# S7CAS-PLEIADES-CARTE-MERE_Pxx_POWER_FPGA.net
KiCad netlist of a schematic drawn in Altium Designer
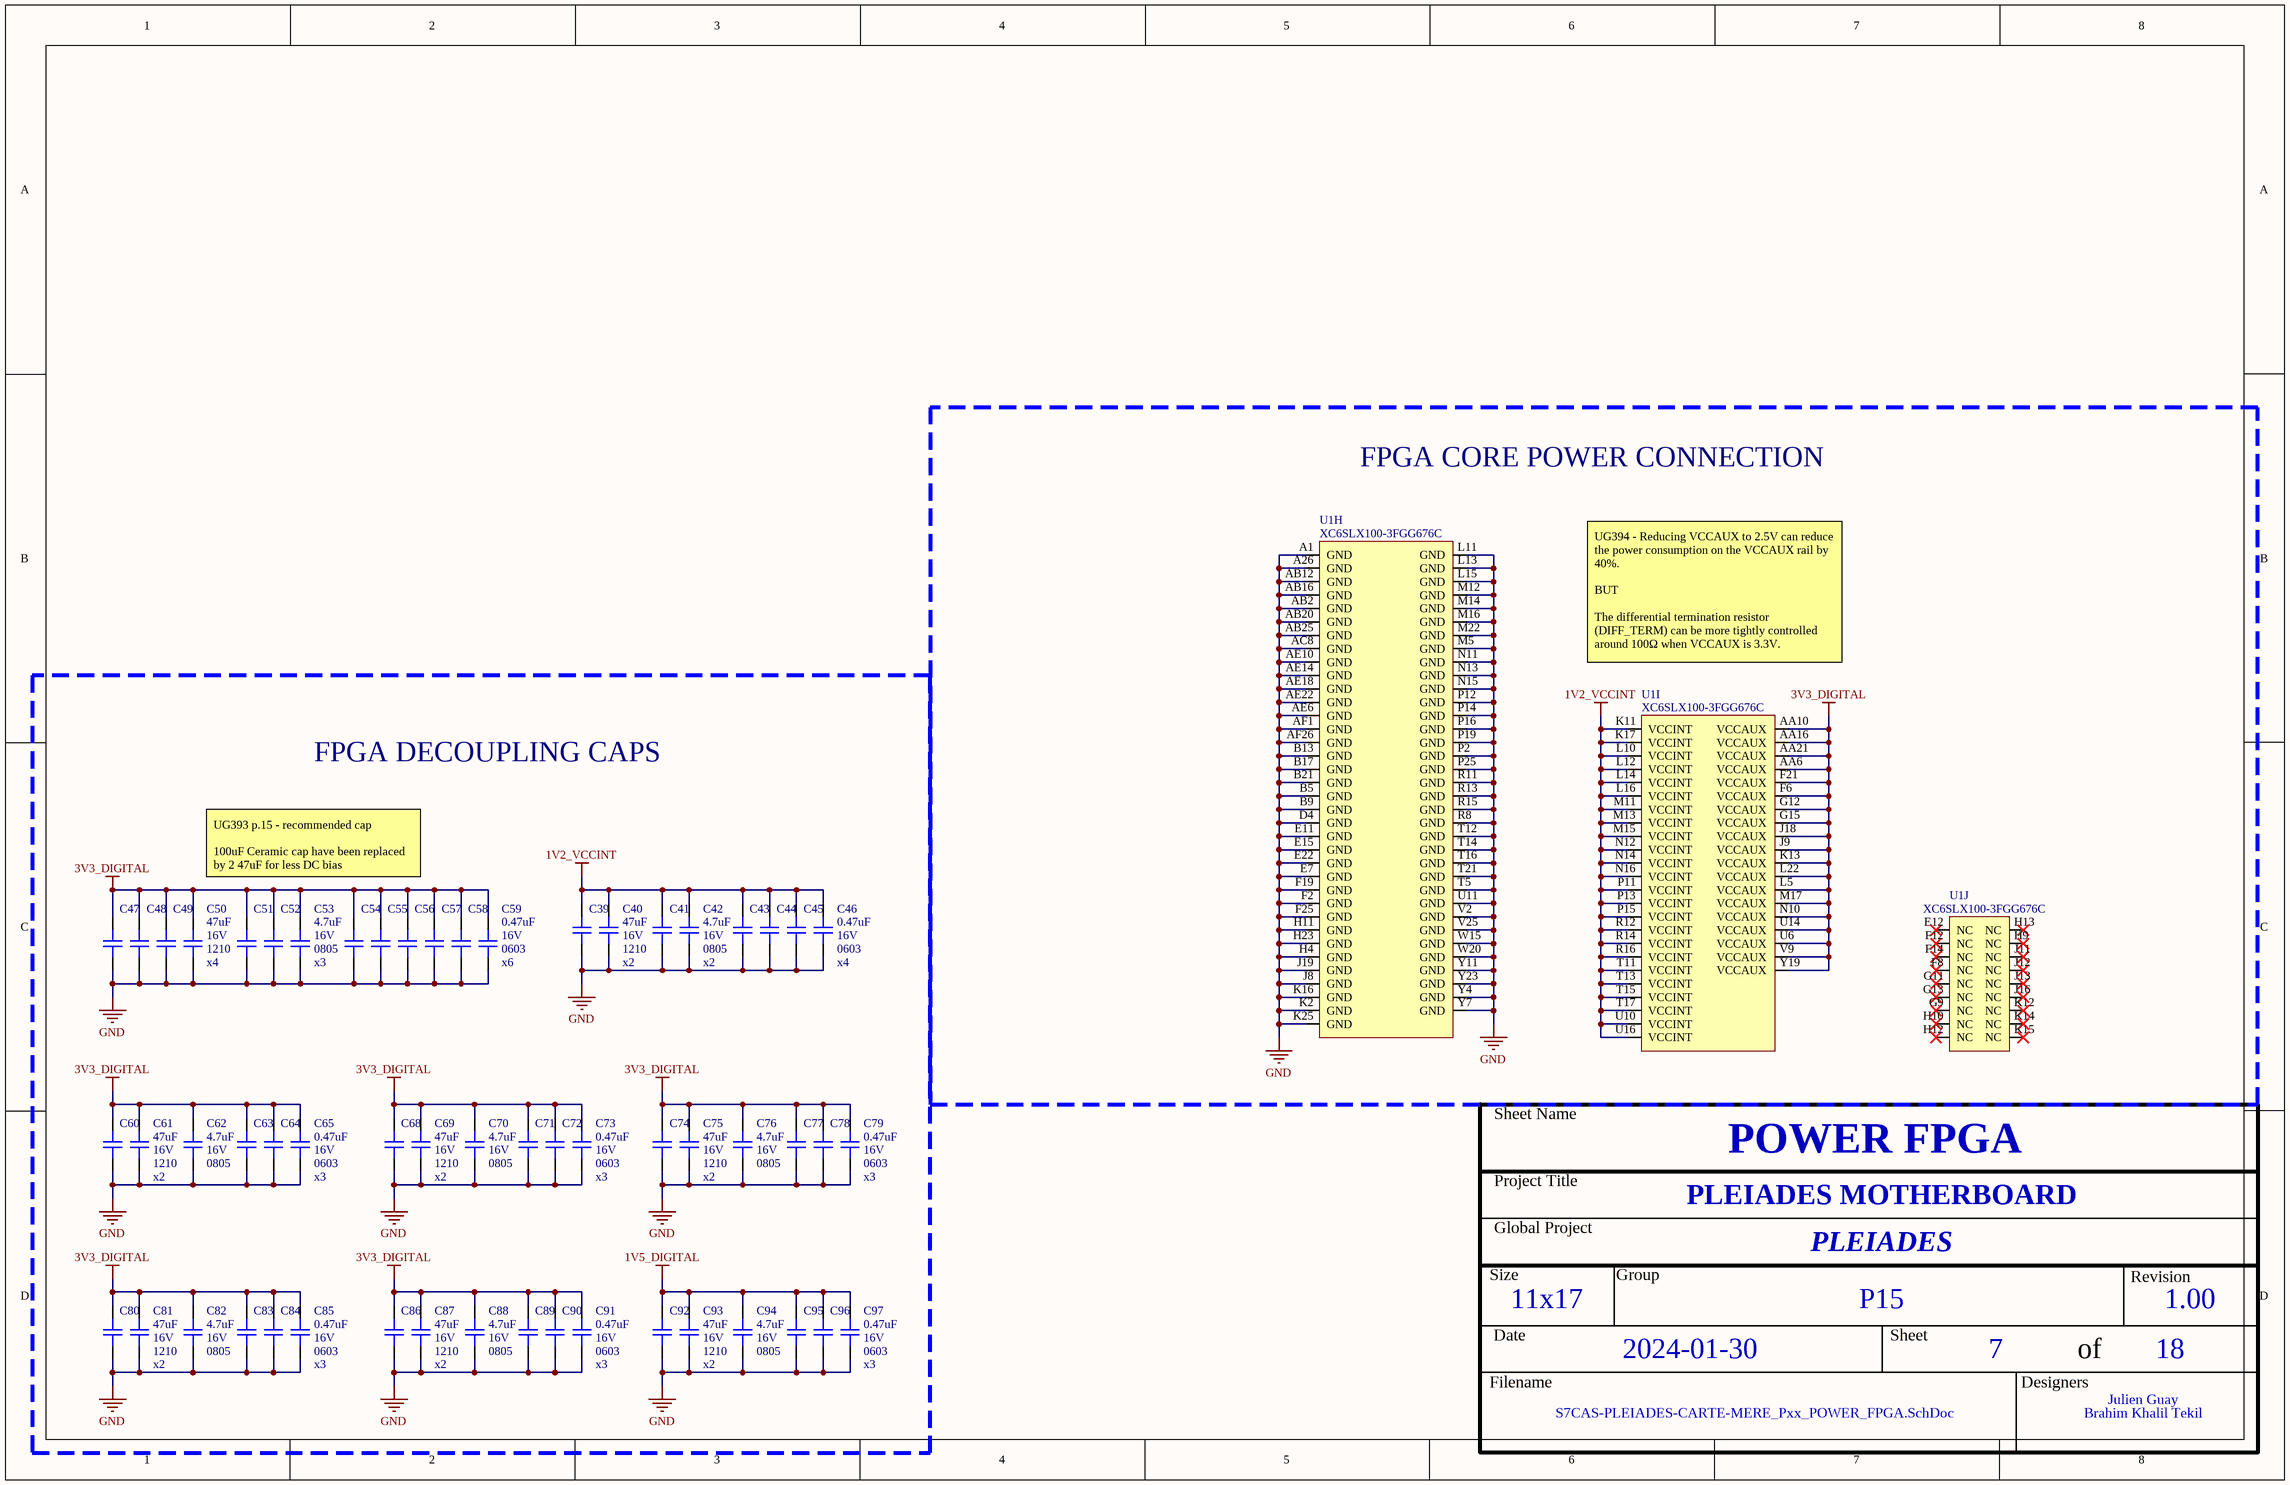
[diagram p0: S7CAS-PLEIADES-CARTE-MERE_Pxx_POWER_FPGA.SchDoc]

(export (version "E")
  (design (tool "Eeschema 10.0.6"))
  (components
    (comp (ref "C39")
      (value "CAP - 1210")
      (footprint "CAP_1210")
      (fields (field (name "VOLTAGE") "16V") (field (name "CREATEDBY") "Jonathan Bouchard"))
      (libsource (lib "S7CAS_LIB2023") (part "CAP - 1210"))
    )
    (comp (ref "C40")
      (value "47uF")
      (footprint "CAP_1210")
      (description "CAP - 1210")
      (fields
        (field (name "VOLTAGE") "16V")
        (field (name "PACKAGE") "1210")
        (field (name "CREATEDBY") "Jonathan Bouchard")
      )
      (libsource (lib "S7CAS_LIB2023") (part "CAP - 1210"))
    )
    (comp (ref "C41")
      (value "CAP - 0805")
      (footprint "CAP_0805")
      (fields (field (name "VOLTAGE") "16V") (field (name "CREATEDBY") "Jonathan Bouchard"))
      (libsource (lib "S7CAS_LIB2023") (part "CAP - 0805"))
    )
    (comp (ref "C42")
      (value "4.7uF")
      (footprint "CAP_0805")
      (description "CAP - 0805")
      (fields
        (field (name "VOLTAGE") "16V")
        (field (name "PACKAGE") "0805")
        (field (name "CREATEDBY") "Jonathan Bouchard")
      )
      (libsource (lib "S7CAS_LIB2023") (part "CAP - 0805"))
    )
    (comp (ref "C43")
      (value "CAP - 0603")
      (footprint "CAP_0603")
      (fields (field (name "VOLTAGE") "16V") (field (name "CREATEDBY") "Jonathan Bouchard"))
      (libsource (lib "S7CAS_LIB2023") (part "CAP - 0603"))
    )
    (comp (ref "C44")
      (value "CAP - 0603")
      (footprint "CAP_0603")
      (fields (field (name "VOLTAGE") "16V") (field (name "CREATEDBY") "Jonathan Bouchard"))
      (libsource (lib "S7CAS_LIB2023") (part "CAP - 0603"))
    )
    (comp (ref "C45")
      (value "CAP - 0603")
      (footprint "CAP_0603")
      (fields (field (name "VOLTAGE") "16V") (field (name "CREATEDBY") "Jonathan Bouchard"))
      (libsource (lib "S7CAS_LIB2023") (part "CAP - 0603"))
    )
    (comp (ref "C46")
      (value "0.47uF")
      (footprint "CAP_0603")
      (description "CAP - 0603")
      (fields
        (field (name "VOLTAGE") "16V")
        (field (name "PACKAGE") "0603")
        (field (name "CREATEDBY") "Jonathan Bouchard")
      )
      (libsource (lib "S7CAS_LIB2023") (part "CAP - 0603"))
    )
    (comp (ref "C47")
      (value "CAP - 1210")
      (footprint "CAP_1210")
      (fields (field (name "VOLTAGE") "16V") (field (name "CREATEDBY") "Jonathan Bouchard"))
      (libsource (lib "S7CAS_LIB2023") (part "CAP - 1210"))
    )
    (comp (ref "C48")
      (value "CAP - 1210")
      (footprint "CAP_1210")
      (fields (field (name "VOLTAGE") "16V") (field (name "CREATEDBY") "Jonathan Bouchard"))
      (libsource (lib "S7CAS_LIB2023") (part "CAP - 1210"))
    )
    (comp (ref "C49")
      (value "CAP - 1210")
      (footprint "CAP_1210")
      (fields (field (name "VOLTAGE") "16V") (field (name "CREATEDBY") "Jonathan Bouchard"))
      (libsource (lib "S7CAS_LIB2023") (part "CAP - 1210"))
    )
    (comp (ref "C50")
      (value "47uF")
      (footprint "CAP_1210")
      (description "CAP - 1210")
      (fields
        (field (name "VOLTAGE") "16V")
        (field (name "PACKAGE") "1210")
        (field (name "CREATEDBY") "Jonathan Bouchard")
      )
      (libsource (lib "S7CAS_LIB2023") (part "CAP - 1210"))
    )
    (comp (ref "C51")
      (value "CAP - 0805")
      (footprint "CAP_0805")
      (fields (field (name "VOLTAGE") "16V") (field (name "CREATEDBY") "Jonathan Bouchard"))
      (libsource (lib "S7CAS_LIB2023") (part "CAP - 0805"))
    )
    (comp (ref "C52")
      (value "CAP - 0805")
      (footprint "CAP_0805")
      (fields (field (name "VOLTAGE") "16V") (field (name "CREATEDBY") "Jonathan Bouchard"))
      (libsource (lib "S7CAS_LIB2023") (part "CAP - 0805"))
    )
    (comp (ref "C53")
      (value "4.7uF")
      (footprint "CAP_0805")
      (description "CAP - 0805")
      (fields
        (field (name "VOLTAGE") "16V")
        (field (name "PACKAGE") "0805")
        (field (name "CREATEDBY") "Jonathan Bouchard")
      )
      (libsource (lib "S7CAS_LIB2023") (part "CAP - 0805"))
    )
    (comp (ref "C54")
      (value "CAP - 0603")
      (footprint "CAP_0603")
      (fields (field (name "VOLTAGE") "16V") (field (name "CREATEDBY") "Jonathan Bouchard"))
      (libsource (lib "S7CAS_LIB2023") (part "CAP - 0603"))
    )
    (comp (ref "C55")
      (value "CAP - 0603")
      (footprint "CAP_0603")
      (fields (field (name "VOLTAGE") "16V") (field (name "CREATEDBY") "Jonathan Bouchard"))
      (libsource (lib "S7CAS_LIB2023") (part "CAP - 0603"))
    )
    (comp (ref "C56")
      (value "CAP - 0603")
      (footprint "CAP_0603")
      (fields (field (name "VOLTAGE") "16V") (field (name "CREATEDBY") "Jonathan Bouchard"))
      (libsource (lib "S7CAS_LIB2023") (part "CAP - 0603"))
    )
    (comp (ref "C57")
      (value "CAP - 0603")
      (footprint "CAP_0603")
      (fields (field (name "VOLTAGE") "16V") (field (name "CREATEDBY") "Jonathan Bouchard"))
      (libsource (lib "S7CAS_LIB2023") (part "CAP - 0603"))
    )
    (comp (ref "C58")
      (value "CAP - 0603")
      (footprint "CAP_0603")
      (fields (field (name "VOLTAGE") "16V") (field (name "CREATEDBY") "Jonathan Bouchard"))
      (libsource (lib "S7CAS_LIB2023") (part "CAP - 0603"))
    )
    (comp (ref "C59")
      (value "0.47uF")
      (footprint "CAP_0603")
      (description "CAP - 0603")
      (fields
        (field (name "VOLTAGE") "16V")
        (field (name "PACKAGE") "0603")
        (field (name "CREATEDBY") "Jonathan Bouchard")
      )
      (libsource (lib "S7CAS_LIB2023") (part "CAP - 0603"))
    )
    (comp (ref "C60")
      (value "CAP - 1210")
      (footprint "CAP_1210")
      (fields (field (name "VOLTAGE") "16V") (field (name "CREATEDBY") "Jonathan Bouchard"))
      (libsource (lib "S7CAS_LIB2023") (part "CAP - 1210"))
    )
    (comp (ref "C61")
      (value "47uF")
      (footprint "CAP_1210")
      (description "CAP - 1210")
      (fields
        (field (name "VOLTAGE") "16V")
        (field (name "PACKAGE") "1210")
        (field (name "CREATEDBY") "Jonathan Bouchard")
      )
      (libsource (lib "S7CAS_LIB2023") (part "CAP - 1210"))
    )
    (comp (ref "C62")
      (value "4.7uF")
      (footprint "CAP_0805")
      (description "CAP - 0805")
      (fields
        (field (name "VOLTAGE") "16V")
        (field (name "PACKAGE") "0805")
        (field (name "CREATEDBY") "Jonathan Bouchard")
      )
      (libsource (lib "S7CAS_LIB2023") (part "CAP - 0805"))
    )
    (comp (ref "C63")
      (value "CAP - 0603")
      (footprint "CAP_0603")
      (fields (field (name "VOLTAGE") "16V") (field (name "CREATEDBY") "Jonathan Bouchard"))
      (libsource (lib "S7CAS_LIB2023") (part "CAP - 0603"))
    )
    (comp (ref "C64")
      (value "CAP - 0603")
      (footprint "CAP_0603")
      (fields (field (name "VOLTAGE") "16V") (field (name "CREATEDBY") "Jonathan Bouchard"))
      (libsource (lib "S7CAS_LIB2023") (part "CAP - 0603"))
    )
    (comp (ref "C65")
      (value "0.47uF")
      (footprint "CAP_0603")
      (description "CAP - 0603")
      (fields
        (field (name "VOLTAGE") "16V")
        (field (name "PACKAGE") "0603")
        (field (name "CREATEDBY") "Jonathan Bouchard")
      )
      (libsource (lib "S7CAS_LIB2023") (part "CAP - 0603"))
    )
    (comp (ref "C68")
      (value "CAP - 1210")
      (footprint "CAP_1210")
      (fields (field (name "VOLTAGE") "16V") (field (name "CREATEDBY") "Jonathan Bouchard"))
      (libsource (lib "S7CAS_LIB2023") (part "CAP - 1210"))
    )
    (comp (ref "C69")
      (value "47uF")
      (footprint "CAP_1210")
      (description "CAP - 1210")
      (fields
        (field (name "VOLTAGE") "16V")
        (field (name "PACKAGE") "1210")
        (field (name "CREATEDBY") "Jonathan Bouchard")
      )
      (libsource (lib "S7CAS_LIB2023") (part "CAP - 1210"))
    )
    (comp (ref "C70")
      (value "4.7uF")
      (footprint "CAP_0805")
      (description "CAP - 0805")
      (fields
        (field (name "VOLTAGE") "16V")
        (field (name "PACKAGE") "0805")
        (field (name "CREATEDBY") "Jonathan Bouchard")
      )
      (libsource (lib "S7CAS_LIB2023") (part "CAP - 0805"))
    )
    (comp (ref "C71")
      (value "CAP - 0603")
      (footprint "CAP_0603")
      (fields (field (name "VOLTAGE") "16V") (field (name "CREATEDBY") "Jonathan Bouchard"))
      (libsource (lib "S7CAS_LIB2023") (part "CAP - 0603"))
    )
    (comp (ref "C72")
      (value "CAP - 0603")
      (footprint "CAP_0603")
      (fields (field (name "VOLTAGE") "16V") (field (name "CREATEDBY") "Jonathan Bouchard"))
      (libsource (lib "S7CAS_LIB2023") (part "CAP - 0603"))
    )
    (comp (ref "C73")
      (value "0.47uF")
      (footprint "CAP_0603")
      (description "CAP - 0603")
      (fields
        (field (name "VOLTAGE") "16V")
        (field (name "PACKAGE") "0603")
        (field (name "CREATEDBY") "Jonathan Bouchard")
      )
      (libsource (lib "S7CAS_LIB2023") (part "CAP - 0603"))
    )
    (comp (ref "C74")
      (value "CAP - 1210")
      (footprint "CAP_1210")
      (fields (field (name "VOLTAGE") "16V") (field (name "CREATEDBY") "Jonathan Bouchard"))
      (libsource (lib "S7CAS_LIB2023") (part "CAP - 1210"))
    )
    (comp (ref "C75")
      (value "47uF")
      (footprint "CAP_1210")
      (description "CAP - 1210")
      (fields
        (field (name "VOLTAGE") "16V")
        (field (name "PACKAGE") "1210")
        (field (name "CREATEDBY") "Jonathan Bouchard")
      )
      (libsource (lib "S7CAS_LIB2023") (part "CAP - 1210"))
    )
    (comp (ref "C76")
      (value "4.7uF")
      (footprint "CAP_0805")
      (description "CAP - 0805")
      (fields
        (field (name "VOLTAGE") "16V")
        (field (name "PACKAGE") "0805")
        (field (name "CREATEDBY") "Jonathan Bouchard")
      )
      (libsource (lib "S7CAS_LIB2023") (part "CAP - 0805"))
    )
    (comp (ref "C77")
      (value "CAP - 0603")
      (footprint "CAP_0603")
      (fields (field (name "VOLTAGE") "16V") (field (name "CREATEDBY") "Jonathan Bouchard"))
      (libsource (lib "S7CAS_LIB2023") (part "CAP - 0603"))
    )
    (comp (ref "C78")
      (value "CAP - 0603")
      (footprint "CAP_0603")
      (fields (field (name "VOLTAGE") "16V") (field (name "CREATEDBY") "Jonathan Bouchard"))
      (libsource (lib "S7CAS_LIB2023") (part "CAP - 0603"))
    )
    (comp (ref "C79")
      (value "0.47uF")
      (footprint "CAP_0603")
      (description "CAP - 0603")
      (fields
        (field (name "VOLTAGE") "16V")
        (field (name "PACKAGE") "0603")
        (field (name "CREATEDBY") "Jonathan Bouchard")
      )
      (libsource (lib "S7CAS_LIB2023") (part "CAP - 0603"))
    )
    (comp (ref "C80")
      (value "CAP - 1210")
      (footprint "CAP_1210")
      (fields (field (name "VOLTAGE") "16V") (field (name "CREATEDBY") "Jonathan Bouchard"))
      (libsource (lib "S7CAS_LIB2023") (part "CAP - 1210"))
    )
    (comp (ref "C81")
      (value "47uF")
      (footprint "CAP_1210")
      (description "CAP - 1210")
      (fields
        (field (name "VOLTAGE") "16V")
        (field (name "PACKAGE") "1210")
        (field (name "CREATEDBY") "Jonathan Bouchard")
      )
      (libsource (lib "S7CAS_LIB2023") (part "CAP - 1210"))
    )
    (comp (ref "C82")
      (value "4.7uF")
      (footprint "CAP_0805")
      (description "CAP - 0805")
      (fields
        (field (name "VOLTAGE") "16V")
        (field (name "PACKAGE") "0805")
        (field (name "CREATEDBY") "Jonathan Bouchard")
      )
      (libsource (lib "S7CAS_LIB2023") (part "CAP - 0805"))
    )
    (comp (ref "C83")
      (value "CAP - 0603")
      (footprint "CAP_0603")
      (fields (field (name "VOLTAGE") "16V") (field (name "CREATEDBY") "Jonathan Bouchard"))
      (libsource (lib "S7CAS_LIB2023") (part "CAP - 0603"))
    )
    (comp (ref "C84")
      (value "CAP - 0603")
      (footprint "CAP_0603")
      (fields (field (name "VOLTAGE") "16V") (field (name "CREATEDBY") "Jonathan Bouchard"))
      (libsource (lib "S7CAS_LIB2023") (part "CAP - 0603"))
    )
    (comp (ref "C85")
      (value "0.47uF")
      (footprint "CAP_0603")
      (description "CAP - 0603")
      (fields
        (field (name "VOLTAGE") "16V")
        (field (name "PACKAGE") "0603")
        (field (name "CREATEDBY") "Jonathan Bouchard")
      )
      (libsource (lib "S7CAS_LIB2023") (part "CAP - 0603"))
    )
    (comp (ref "C86")
      (value "CAP - 1210")
      (footprint "CAP_1210")
      (fields (field (name "VOLTAGE") "16V") (field (name "CREATEDBY") "Jonathan Bouchard"))
      (libsource (lib "S7CAS_LIB2023") (part "CAP - 1210"))
    )
    (comp (ref "C87")
      (value "47uF")
      (footprint "CAP_1210")
      (description "CAP - 1210")
      (fields
        (field (name "VOLTAGE") "16V")
        (field (name "PACKAGE") "1210")
        (field (name "CREATEDBY") "Jonathan Bouchard")
      )
      (libsource (lib "S7CAS_LIB2023") (part "CAP - 1210"))
    )
    (comp (ref "C88")
      (value "4.7uF")
      (footprint "CAP_0805")
      (description "CAP - 0805")
      (fields
        (field (name "VOLTAGE") "16V")
        (field (name "PACKAGE") "0805")
        (field (name "CREATEDBY") "Jonathan Bouchard")
      )
      (libsource (lib "S7CAS_LIB2023") (part "CAP - 0805"))
    )
    (comp (ref "C89")
      (value "CAP - 0603")
      (footprint "CAP_0603")
      (fields (field (name "VOLTAGE") "16V") (field (name "CREATEDBY") "Jonathan Bouchard"))
      (libsource (lib "S7CAS_LIB2023") (part "CAP - 0603"))
    )
    (comp (ref "C90")
      (value "CAP - 0603")
      (footprint "CAP_0603")
      (fields (field (name "VOLTAGE") "16V") (field (name "CREATEDBY") "Jonathan Bouchard"))
      (libsource (lib "S7CAS_LIB2023") (part "CAP - 0603"))
    )
    (comp (ref "C91")
      (value "0.47uF")
      (footprint "CAP_0603")
      (description "CAP - 0603")
      (fields
        (field (name "VOLTAGE") "16V")
        (field (name "PACKAGE") "0603")
        (field (name "CREATEDBY") "Jonathan Bouchard")
      )
      (libsource (lib "S7CAS_LIB2023") (part "CAP - 0603"))
    )
    (comp (ref "C92")
      (value "CAP - 1210")
      (footprint "CAP_1210")
      (fields (field (name "VOLTAGE") "16V") (field (name "CREATEDBY") "Jonathan Bouchard"))
      (libsource (lib "S7CAS_LIB2023") (part "CAP - 1210"))
    )
    (comp (ref "C93")
      (value "47uF")
      (footprint "CAP_1210")
      (description "CAP - 1210")
      (fields
        (field (name "VOLTAGE") "16V")
        (field (name "PACKAGE") "1210")
        (field (name "CREATEDBY") "Jonathan Bouchard")
      )
      (libsource (lib "S7CAS_LIB2023") (part "CAP - 1210"))
    )
    (comp (ref "C94")
      (value "4.7uF")
      (footprint "CAP_0805")
      (description "CAP - 0805")
      (fields
        (field (name "VOLTAGE") "16V")
        (field (name "PACKAGE") "0805")
        (field (name "CREATEDBY") "Jonathan Bouchard")
      )
      (libsource (lib "S7CAS_LIB2023") (part "CAP - 0805"))
    )
    (comp (ref "C95")
      (value "CAP - 0603")
      (footprint "CAP_0603")
      (fields (field (name "VOLTAGE") "16V") (field (name "CREATEDBY") "Jonathan Bouchard"))
      (libsource (lib "S7CAS_LIB2023") (part "CAP - 0603"))
    )
    (comp (ref "C96")
      (value "CAP - 0603")
      (footprint "CAP_0603")
      (fields (field (name "VOLTAGE") "16V") (field (name "CREATEDBY") "Jonathan Bouchard"))
      (libsource (lib "S7CAS_LIB2023") (part "CAP - 0603"))
    )
    (comp (ref "C97")
      (value "0.47uF")
      (footprint "CAP_0603")
      (description "CAP - 0603")
      (fields
        (field (name "VOLTAGE") "16V")
        (field (name "PACKAGE") "0603")
        (field (name "CREATEDBY") "Jonathan Bouchard")
      )
      (libsource (lib "S7CAS_LIB2023") (part "CAP - 0603"))
    )
    (comp (ref "U1")
      (value "XC6SLX100-3FGG676C")
      (footprint "FPGA_XILINX_FGG676")
      (description "FPGA - XILINX SPARTAN 6 480 I/O - BGA-676")
      (fields
        (field (name "VOLTAGE") "1.14 V ~ 1.26 V")
        (field (name "MFG") "Xilinx")
        (field (name "CREATEDBY") "Jonathan Bouchard")
      )
      (libsource (lib "S7CAS_LIB2023") (part "FPGA_XC6SLX100-3FGG676C"))
    )
  )
  (nets
    (net (code "1") (name "1V2_VCCINT") (class "Default")
      (node (ref "C39") (pin "2") (pinfunction "2_2") (pintype "passive"))
      (node (ref "C40") (pin "2") (pinfunction "2_2") (pintype "passive"))
      (node (ref "C41") (pin "2") (pinfunction "2_2") (pintype "passive"))
      (node (ref "C42") (pin "2") (pinfunction "2_2") (pintype "passive"))
      (node (ref "C43") (pin "2") (pinfunction "2_2") (pintype "passive"))
      (node (ref "C44") (pin "2") (pinfunction "2_2") (pintype "passive"))
      (node (ref "C45") (pin "2") (pinfunction "2_2") (pintype "passive"))
      (node (ref "C46") (pin "2") (pinfunction "2_2") (pintype "passive"))
      (node (ref "U1") (pin "K11") (pinfunction "VCCINT_K11") (pintype "passive"))
      (node (ref "U1") (pin "K17") (pinfunction "VCCINT_K17") (pintype "passive"))
      (node (ref "U1") (pin "L10") (pinfunction "VCCINT_L10") (pintype "passive"))
      (node (ref "U1") (pin "L12") (pinfunction "VCCINT_L12") (pintype "passive"))
      (node (ref "U1") (pin "L14") (pinfunction "VCCINT_L14") (pintype "passive"))
      (node (ref "U1") (pin "L16") (pinfunction "VCCINT_L16") (pintype "passive"))
      (node (ref "U1") (pin "M11") (pinfunction "VCCINT_M11") (pintype "passive"))
      (node (ref "U1") (pin "M13") (pinfunction "VCCINT_M13") (pintype "passive"))
      (node (ref "U1") (pin "M15") (pinfunction "VCCINT_M15") (pintype "passive"))
      (node (ref "U1") (pin "N12") (pinfunction "VCCINT_N12") (pintype "passive"))
      (node (ref "U1") (pin "N14") (pinfunction "VCCINT_N14") (pintype "passive"))
      (node (ref "U1") (pin "N16") (pinfunction "VCCINT_N16") (pintype "passive"))
      (node (ref "U1") (pin "P11") (pinfunction "VCCINT_P11") (pintype "passive"))
      (node (ref "U1") (pin "P13") (pinfunction "VCCINT_P13") (pintype "passive"))
      (node (ref "U1") (pin "P15") (pinfunction "VCCINT_P15") (pintype "passive"))
      (node (ref "U1") (pin "R12") (pinfunction "VCCINT_R12") (pintype "passive"))
      (node (ref "U1") (pin "R14") (pinfunction "VCCINT_R14") (pintype "passive"))
      (node (ref "U1") (pin "R16") (pinfunction "VCCINT_R16") (pintype "passive"))
      (node (ref "U1") (pin "T11") (pinfunction "VCCINT_T11") (pintype "passive"))
      (node (ref "U1") (pin "T13") (pinfunction "VCCINT_T13") (pintype "passive"))
      (node (ref "U1") (pin "T15") (pinfunction "VCCINT_T15") (pintype "passive"))
      (node (ref "U1") (pin "T17") (pinfunction "VCCINT_T17") (pintype "passive"))
      (node (ref "U1") (pin "U10") (pinfunction "VCCINT_U10") (pintype "passive"))
      (node (ref "U1") (pin "U16") (pinfunction "VCCINT_U16") (pintype "passive"))
    )
    (net (code "2") (name "1V5_DIGITAL") (class "Default")
      (node (ref "C92") (pin "2") (pinfunction "2_2") (pintype "passive"))
      (node (ref "C93") (pin "2") (pinfunction "2_2") (pintype "passive"))
      (node (ref "C94") (pin "2") (pinfunction "2_2") (pintype "passive"))
      (node (ref "C95") (pin "2") (pinfunction "2_2") (pintype "passive"))
      (node (ref "C96") (pin "2") (pinfunction "2_2") (pintype "passive"))
      (node (ref "C97") (pin "2") (pinfunction "2_2") (pintype "passive"))
    )
    (net (code "3") (name "3V3_DIGITAL") (class "Default")
      (node (ref "C47") (pin "2") (pinfunction "2_2") (pintype "passive"))
      (node (ref "C48") (pin "2") (pinfunction "2_2") (pintype "passive"))
      (node (ref "C49") (pin "2") (pinfunction "2_2") (pintype "passive"))
      (node (ref "C50") (pin "2") (pinfunction "2_2") (pintype "passive"))
      (node (ref "C51") (pin "2") (pinfunction "2_2") (pintype "passive"))
      (node (ref "C52") (pin "2") (pinfunction "2_2") (pintype "passive"))
      (node (ref "C53") (pin "2") (pinfunction "2_2") (pintype "passive"))
      (node (ref "C54") (pin "2") (pinfunction "2_2") (pintype "passive"))
      (node (ref "C55") (pin "2") (pinfunction "2_2") (pintype "passive"))
      (node (ref "C56") (pin "2") (pinfunction "2_2") (pintype "passive"))
      (node (ref "C57") (pin "2") (pinfunction "2_2") (pintype "passive"))
      (node (ref "C58") (pin "2") (pinfunction "2_2") (pintype "passive"))
      (node (ref "C59") (pin "2") (pinfunction "2_2") (pintype "passive"))
      (node (ref "C60") (pin "2") (pinfunction "2_2") (pintype "passive"))
      (node (ref "C61") (pin "2") (pinfunction "2_2") (pintype "passive"))
      (node (ref "C62") (pin "2") (pinfunction "2_2") (pintype "passive"))
      (node (ref "C63") (pin "2") (pinfunction "2_2") (pintype "passive"))
      (node (ref "C64") (pin "2") (pinfunction "2_2") (pintype "passive"))
      (node (ref "C65") (pin "2") (pinfunction "2_2") (pintype "passive"))
      (node (ref "C68") (pin "2") (pinfunction "2_2") (pintype "passive"))
      (node (ref "C69") (pin "2") (pinfunction "2_2") (pintype "passive"))
      (node (ref "C70") (pin "2") (pinfunction "2_2") (pintype "passive"))
      (node (ref "C71") (pin "2") (pinfunction "2_2") (pintype "passive"))
      (node (ref "C72") (pin "2") (pinfunction "2_2") (pintype "passive"))
      (node (ref "C73") (pin "2") (pinfunction "2_2") (pintype "passive"))
      (node (ref "C74") (pin "2") (pinfunction "2_2") (pintype "passive"))
      (node (ref "C75") (pin "2") (pinfunction "2_2") (pintype "passive"))
      (node (ref "C76") (pin "2") (pinfunction "2_2") (pintype "passive"))
      (node (ref "C77") (pin "2") (pinfunction "2_2") (pintype "passive"))
      (node (ref "C78") (pin "2") (pinfunction "2_2") (pintype "passive"))
      (node (ref "C79") (pin "2") (pinfunction "2_2") (pintype "passive"))
      (node (ref "C80") (pin "2") (pinfunction "2_2") (pintype "passive"))
      (node (ref "C81") (pin "2") (pinfunction "2_2") (pintype "passive"))
      (node (ref "C82") (pin "2") (pinfunction "2_2") (pintype "passive"))
      (node (ref "C83") (pin "2") (pinfunction "2_2") (pintype "passive"))
      (node (ref "C84") (pin "2") (pinfunction "2_2") (pintype "passive"))
      (node (ref "C85") (pin "2") (pinfunction "2_2") (pintype "passive"))
      (node (ref "C86") (pin "2") (pinfunction "2_2") (pintype "passive"))
      (node (ref "C87") (pin "2") (pinfunction "2_2") (pintype "passive"))
      (node (ref "C88") (pin "2") (pinfunction "2_2") (pintype "passive"))
      (node (ref "C89") (pin "2") (pinfunction "2_2") (pintype "passive"))
      (node (ref "C90") (pin "2") (pinfunction "2_2") (pintype "passive"))
      (node (ref "C91") (pin "2") (pinfunction "2_2") (pintype "passive"))
      (node (ref "U1") (pin "AA10") (pinfunction "VCCAUX_AA10") (pintype "passive"))
      (node (ref "U1") (pin "AA16") (pinfunction "VCCAUX_AA16") (pintype "passive"))
      (node (ref "U1") (pin "AA21") (pinfunction "VCCAUX_AA21") (pintype "passive"))
      (node (ref "U1") (pin "AA6") (pinfunction "VCCAUX_AA6") (pintype "passive"))
      (node (ref "U1") (pin "F21") (pinfunction "VCCAUX_F21") (pintype "passive"))
      (node (ref "U1") (pin "F6") (pinfunction "VCCAUX_F6") (pintype "passive"))
      (node (ref "U1") (pin "G12") (pinfunction "VCCAUX_G12") (pintype "passive"))
      (node (ref "U1") (pin "G15") (pinfunction "VCCAUX_G15") (pintype "passive"))
      (node (ref "U1") (pin "J18") (pinfunction "VCCAUX_J18") (pintype "passive"))
      (node (ref "U1") (pin "J9") (pinfunction "VCCAUX_J9") (pintype "passive"))
      (node (ref "U1") (pin "K13") (pinfunction "VCCAUX_K13") (pintype "passive"))
      (node (ref "U1") (pin "L22") (pinfunction "VCCAUX_L22") (pintype "passive"))
      (node (ref "U1") (pin "L5") (pinfunction "VCCAUX_L5") (pintype "passive"))
      (node (ref "U1") (pin "M17") (pinfunction "VCCAUX_M17") (pintype "passive"))
      (node (ref "U1") (pin "N10") (pinfunction "VCCAUX_N10") (pintype "passive"))
      (node (ref "U1") (pin "U14") (pinfunction "VCCAUX_U14") (pintype "passive"))
      (node (ref "U1") (pin "U6") (pinfunction "VCCAUX_U6") (pintype "passive"))
      (node (ref "U1") (pin "V9") (pinfunction "VCCAUX_V9") (pintype "passive"))
      (node (ref "U1") (pin "Y19") (pinfunction "VCCAUX_Y19") (pintype "passive"))
    )
    (net (code "4") (name "GND") (class "Default")
      (node (ref "C39") (pin "1") (pinfunction "1_1") (pintype "passive"))
      (node (ref "C40") (pin "1") (pinfunction "1_1") (pintype "passive"))
      (node (ref "C41") (pin "1") (pinfunction "1_1") (pintype "passive"))
      (node (ref "C42") (pin "1") (pinfunction "1_1") (pintype "passive"))
      (node (ref "C43") (pin "1") (pinfunction "1_1") (pintype "passive"))
      (node (ref "C44") (pin "1") (pinfunction "1_1") (pintype "passive"))
      (node (ref "C45") (pin "1") (pinfunction "1_1") (pintype "passive"))
      (node (ref "C46") (pin "1") (pinfunction "1_1") (pintype "passive"))
      (node (ref "C47") (pin "1") (pinfunction "1_1") (pintype "passive"))
      (node (ref "C48") (pin "1") (pinfunction "1_1") (pintype "passive"))
      (node (ref "C49") (pin "1") (pinfunction "1_1") (pintype "passive"))
      (node (ref "C50") (pin "1") (pinfunction "1_1") (pintype "passive"))
      (node (ref "C51") (pin "1") (pinfunction "1_1") (pintype "passive"))
      (node (ref "C52") (pin "1") (pinfunction "1_1") (pintype "passive"))
      (node (ref "C53") (pin "1") (pinfunction "1_1") (pintype "passive"))
      (node (ref "C54") (pin "1") (pinfunction "1_1") (pintype "passive"))
      (node (ref "C55") (pin "1") (pinfunction "1_1") (pintype "passive"))
      (node (ref "C56") (pin "1") (pinfunction "1_1") (pintype "passive"))
      (node (ref "C57") (pin "1") (pinfunction "1_1") (pintype "passive"))
      (node (ref "C58") (pin "1") (pinfunction "1_1") (pintype "passive"))
      (node (ref "C59") (pin "1") (pinfunction "1_1") (pintype "passive"))
      (node (ref "C60") (pin "1") (pinfunction "1_1") (pintype "passive"))
      (node (ref "C61") (pin "1") (pinfunction "1_1") (pintype "passive"))
      (node (ref "C62") (pin "1") (pinfunction "1_1") (pintype "passive"))
      (node (ref "C63") (pin "1") (pinfunction "1_1") (pintype "passive"))
      (node (ref "C64") (pin "1") (pinfunction "1_1") (pintype "passive"))
      (node (ref "C65") (pin "1") (pinfunction "1_1") (pintype "passive"))
      (node (ref "C68") (pin "1") (pinfunction "1_1") (pintype "passive"))
      (node (ref "C69") (pin "1") (pinfunction "1_1") (pintype "passive"))
      (node (ref "C70") (pin "1") (pinfunction "1_1") (pintype "passive"))
      (node (ref "C71") (pin "1") (pinfunction "1_1") (pintype "passive"))
      (node (ref "C72") (pin "1") (pinfunction "1_1") (pintype "passive"))
      (node (ref "C73") (pin "1") (pinfunction "1_1") (pintype "passive"))
      (node (ref "C74") (pin "1") (pinfunction "1_1") (pintype "passive"))
      (node (ref "C75") (pin "1") (pinfunction "1_1") (pintype "passive"))
      (node (ref "C76") (pin "1") (pinfunction "1_1") (pintype "passive"))
      (node (ref "C77") (pin "1") (pinfunction "1_1") (pintype "passive"))
      (node (ref "C78") (pin "1") (pinfunction "1_1") (pintype "passive"))
      (node (ref "C79") (pin "1") (pinfunction "1_1") (pintype "passive"))
      (node (ref "C80") (pin "1") (pinfunction "1_1") (pintype "passive"))
      (node (ref "C81") (pin "1") (pinfunction "1_1") (pintype "passive"))
      (node (ref "C82") (pin "1") (pinfunction "1_1") (pintype "passive"))
      (node (ref "C83") (pin "1") (pinfunction "1_1") (pintype "passive"))
      (node (ref "C84") (pin "1") (pinfunction "1_1") (pintype "passive"))
      (node (ref "C85") (pin "1") (pinfunction "1_1") (pintype "passive"))
      (node (ref "C86") (pin "1") (pinfunction "1_1") (pintype "passive"))
      (node (ref "C87") (pin "1") (pinfunction "1_1") (pintype "passive"))
      (node (ref "C88") (pin "1") (pinfunction "1_1") (pintype "passive"))
      (node (ref "C89") (pin "1") (pinfunction "1_1") (pintype "passive"))
      (node (ref "C90") (pin "1") (pinfunction "1_1") (pintype "passive"))
      (node (ref "C91") (pin "1") (pinfunction "1_1") (pintype "passive"))
      (node (ref "C92") (pin "1") (pinfunction "1_1") (pintype "passive"))
      (node (ref "C93") (pin "1") (pinfunction "1_1") (pintype "passive"))
      (node (ref "C94") (pin "1") (pinfunction "1_1") (pintype "passive"))
      (node (ref "C95") (pin "1") (pinfunction "1_1") (pintype "passive"))
      (node (ref "C96") (pin "1") (pinfunction "1_1") (pintype "passive"))
      (node (ref "C97") (pin "1") (pinfunction "1_1") (pintype "passive"))
      (node (ref "U1") (pin "A1") (pinfunction "GND_A1") (pintype "passive"))
      (node (ref "U1") (pin "A26") (pinfunction "GND_A26") (pintype "passive"))
      (node (ref "U1") (pin "AB12") (pinfunction "GND_AB12") (pintype "passive"))
      (node (ref "U1") (pin "AB16") (pinfunction "GND_AB16") (pintype "passive"))
      (node (ref "U1") (pin "AB2") (pinfunction "GND_AB2") (pintype "passive"))
      (node (ref "U1") (pin "AB20") (pinfunction "GND_AB20") (pintype "passive"))
      (node (ref "U1") (pin "AB25") (pinfunction "GND_AB25") (pintype "passive"))
      (node (ref "U1") (pin "AC8") (pinfunction "GND_AC8") (pintype "passive"))
      (node (ref "U1") (pin "AE10") (pinfunction "GND_AE10") (pintype "passive"))
      (node (ref "U1") (pin "AE14") (pinfunction "GND_AE14") (pintype "passive"))
      (node (ref "U1") (pin "AE18") (pinfunction "GND_AE18") (pintype "passive"))
      (node (ref "U1") (pin "AE22") (pinfunction "GND_AE22") (pintype "passive"))
      (node (ref "U1") (pin "AE6") (pinfunction "GND_AE6") (pintype "passive"))
      (node (ref "U1") (pin "AF1") (pinfunction "GND_AF1") (pintype "passive"))
      (node (ref "U1") (pin "AF26") (pinfunction "GND_AF26") (pintype "passive"))
      (node (ref "U1") (pin "B13") (pinfunction "GND_B13") (pintype "passive"))
      (node (ref "U1") (pin "B17") (pinfunction "GND_B17") (pintype "passive"))
      (node (ref "U1") (pin "B21") (pinfunction "GND_B21") (pintype "passive"))
      (node (ref "U1") (pin "B5") (pinfunction "GND_B5") (pintype "passive"))
      (node (ref "U1") (pin "B9") (pinfunction "GND_B9") (pintype "passive"))
      (node (ref "U1") (pin "D4") (pinfunction "GND_D4") (pintype "passive"))
      (node (ref "U1") (pin "E11") (pinfunction "GND_E11") (pintype "passive"))
      (node (ref "U1") (pin "E15") (pinfunction "GND_E15") (pintype "passive"))
      (node (ref "U1") (pin "E22") (pinfunction "GND_E22") (pintype "passive"))
      (node (ref "U1") (pin "E7") (pinfunction "GND_E7") (pintype "passive"))
      (node (ref "U1") (pin "F19") (pinfunction "GND_F19") (pintype "passive"))
      (node (ref "U1") (pin "F2") (pinfunction "GND_F2") (pintype "passive"))
      (node (ref "U1") (pin "F25") (pinfunction "GND_F25") (pintype "passive"))
      (node (ref "U1") (pin "H11") (pinfunction "GND_H11") (pintype "passive"))
      (node (ref "U1") (pin "H23") (pinfunction "GND_H23") (pintype "passive"))
      (node (ref "U1") (pin "H4") (pinfunction "GND_H4") (pintype "passive"))
      (node (ref "U1") (pin "J19") (pinfunction "GND_J19") (pintype "passive"))
      (node (ref "U1") (pin "J8") (pinfunction "GND_J8") (pintype "passive"))
      (node (ref "U1") (pin "K16") (pinfunction "GND_K16") (pintype "passive"))
      (node (ref "U1") (pin "K2") (pinfunction "GND_K2") (pintype "passive"))
      (node (ref "U1") (pin "K25") (pinfunction "GND_K25") (pintype "passive"))
      (node (ref "U1") (pin "L11") (pinfunction "GND_L11") (pintype "passive"))
      (node (ref "U1") (pin "L13") (pinfunction "GND_L13") (pintype "passive"))
      (node (ref "U1") (pin "L15") (pinfunction "GND_L15") (pintype "passive"))
      (node (ref "U1") (pin "M12") (pinfunction "GND_M12") (pintype "passive"))
      (node (ref "U1") (pin "M14") (pinfunction "GND_M14") (pintype "passive"))
      (node (ref "U1") (pin "M16") (pinfunction "GND_M16") (pintype "passive"))
      (node (ref "U1") (pin "M22") (pinfunction "GND_M22") (pintype "passive"))
      (node (ref "U1") (pin "M5") (pinfunction "GND_M5") (pintype "passive"))
      (node (ref "U1") (pin "N11") (pinfunction "GND_N11") (pintype "passive"))
      (node (ref "U1") (pin "N13") (pinfunction "GND_N13") (pintype "passive"))
      (node (ref "U1") (pin "N15") (pinfunction "GND_N15") (pintype "passive"))
      (node (ref "U1") (pin "P12") (pinfunction "GND_P12") (pintype "passive"))
      (node (ref "U1") (pin "P14") (pinfunction "GND_P14") (pintype "passive"))
      (node (ref "U1") (pin "P16") (pinfunction "GND_P16") (pintype "passive"))
      (node (ref "U1") (pin "P19") (pinfunction "GND_P19") (pintype "passive"))
      (node (ref "U1") (pin "P2") (pinfunction "GND_P2") (pintype "passive"))
      (node (ref "U1") (pin "P25") (pinfunction "GND_P25") (pintype "passive"))
      (node (ref "U1") (pin "R11") (pinfunction "GND_R11") (pintype "passive"))
      (node (ref "U1") (pin "R13") (pinfunction "GND_R13") (pintype "passive"))
      (node (ref "U1") (pin "R15") (pinfunction "GND_R15") (pintype "passive"))
      (node (ref "U1") (pin "R8") (pinfunction "GND_R8") (pintype "passive"))
      (node (ref "U1") (pin "T12") (pinfunction "GND_T12") (pintype "passive"))
      (node (ref "U1") (pin "T14") (pinfunction "GND_T14") (pintype "passive"))
      (node (ref "U1") (pin "T16") (pinfunction "GND_T16") (pintype "passive"))
      (node (ref "U1") (pin "T21") (pinfunction "GND_T21") (pintype "passive"))
      (node (ref "U1") (pin "T5") (pinfunction "GND_T5") (pintype "passive"))
      (node (ref "U1") (pin "U11") (pinfunction "GND_U11") (pintype "passive"))
      (node (ref "U1") (pin "V2") (pinfunction "GND_V2") (pintype "passive"))
      (node (ref "U1") (pin "V25") (pinfunction "GND_V25") (pintype "passive"))
      (node (ref "U1") (pin "W15") (pinfunction "GND_W15") (pintype "passive"))
      (node (ref "U1") (pin "W20") (pinfunction "GND_W20") (pintype "passive"))
      (node (ref "U1") (pin "Y11") (pinfunction "GND_Y11") (pintype "passive"))
      (node (ref "U1") (pin "Y23") (pinfunction "GND_Y23") (pintype "passive"))
      (node (ref "U1") (pin "Y4") (pinfunction "GND_Y4") (pintype "passive"))
      (node (ref "U1") (pin "Y7") (pinfunction "GND_Y7") (pintype "passive"))
    )
    (net (code "5") (name "unconnected-(U1J-NC-PadE12)") (class "Default")
      (node (ref "U1") (pin "E12") (pinfunction "NC_E12") (pintype "passive+no_connect"))
    )
    (net (code "6") (name "unconnected-(U1J-NC-PadF8)") (class "Default")
      (node (ref "U1") (pin "F8") (pinfunction "NC_F8") (pintype "passive+no_connect"))
    )
    (net (code "7") (name "unconnected-(U1J-NC-PadF12)") (class "Default")
      (node (ref "U1") (pin "F12") (pinfunction "NC_F12") (pintype "passive+no_connect"))
    )
    (net (code "8") (name "unconnected-(U1J-NC-PadF14)") (class "Default")
      (node (ref "U1") (pin "F14") (pinfunction "NC_F14") (pintype "passive+no_connect"))
    )
    (net (code "9") (name "unconnected-(U1J-NC-PadG9)") (class "Default")
      (node (ref "U1") (pin "G9") (pinfunction "NC_G9") (pintype "passive+no_connect"))
    )
    (net (code "10") (name "unconnected-(U1J-NC-PadG11)") (class "Default")
      (node (ref "U1") (pin "G11") (pinfunction "NC_G11") (pintype "passive+no_connect"))
    )
    (net (code "11") (name "unconnected-(U1J-NC-PadG13)") (class "Default")
      (node (ref "U1") (pin "G13") (pinfunction "NC_G13") (pintype "passive+no_connect"))
    )
    (net (code "12") (name "unconnected-(U1J-NC-PadH9)") (class "Default")
      (node (ref "U1") (pin "H9") (pinfunction "NC_H9") (pintype "passive+no_connect"))
    )
    (net (code "13") (name "unconnected-(U1J-NC-PadH10)") (class "Default")
      (node (ref "U1") (pin "H10") (pinfunction "NC_H10") (pintype "passive+no_connect"))
    )
    (net (code "14") (name "unconnected-(U1J-NC-PadH12)") (class "Default")
      (node (ref "U1") (pin "H12") (pinfunction "NC_H12") (pintype "passive+no_connect"))
    )
    (net (code "15") (name "unconnected-(U1J-NC-PadH13)") (class "Default")
      (node (ref "U1") (pin "H13") (pinfunction "NC_H13") (pintype "passive+no_connect"))
    )
    (net (code "16") (name "unconnected-(U1J-NC-PadJ11)") (class "Default")
      (node (ref "U1") (pin "J11") (pinfunction "NC_J11") (pintype "passive+no_connect"))
    )
    (net (code "17") (name "unconnected-(U1J-NC-PadJ12)") (class "Default")
      (node (ref "U1") (pin "J12") (pinfunction "NC_J12") (pintype "passive+no_connect"))
    )
    (net (code "18") (name "unconnected-(U1J-NC-PadJ13)") (class "Default")
      (node (ref "U1") (pin "J13") (pinfunction "NC_J13") (pintype "passive+no_connect"))
    )
    (net (code "19") (name "unconnected-(U1J-NC-PadJ16)") (class "Default")
      (node (ref "U1") (pin "J16") (pinfunction "NC_J16") (pintype "passive+no_connect"))
    )
    (net (code "20") (name "unconnected-(U1J-NC-PadK12)") (class "Default")
      (node (ref "U1") (pin "K12") (pinfunction "NC_K12") (pintype "passive+no_connect"))
    )
    (net (code "21") (name "unconnected-(U1J-NC-PadK14)") (class "Default")
      (node (ref "U1") (pin "K14") (pinfunction "NC_K14") (pintype "passive+no_connect"))
    )
    (net (code "22") (name "unconnected-(U1J-NC-PadK15)") (class "Default")
      (node (ref "U1") (pin "K15") (pinfunction "NC_K15") (pintype "passive+no_connect"))
    )
  )
)
